# 6__FAN_ADC_LED.net
KiCad netlist of a schematic drawn in Altium Designer
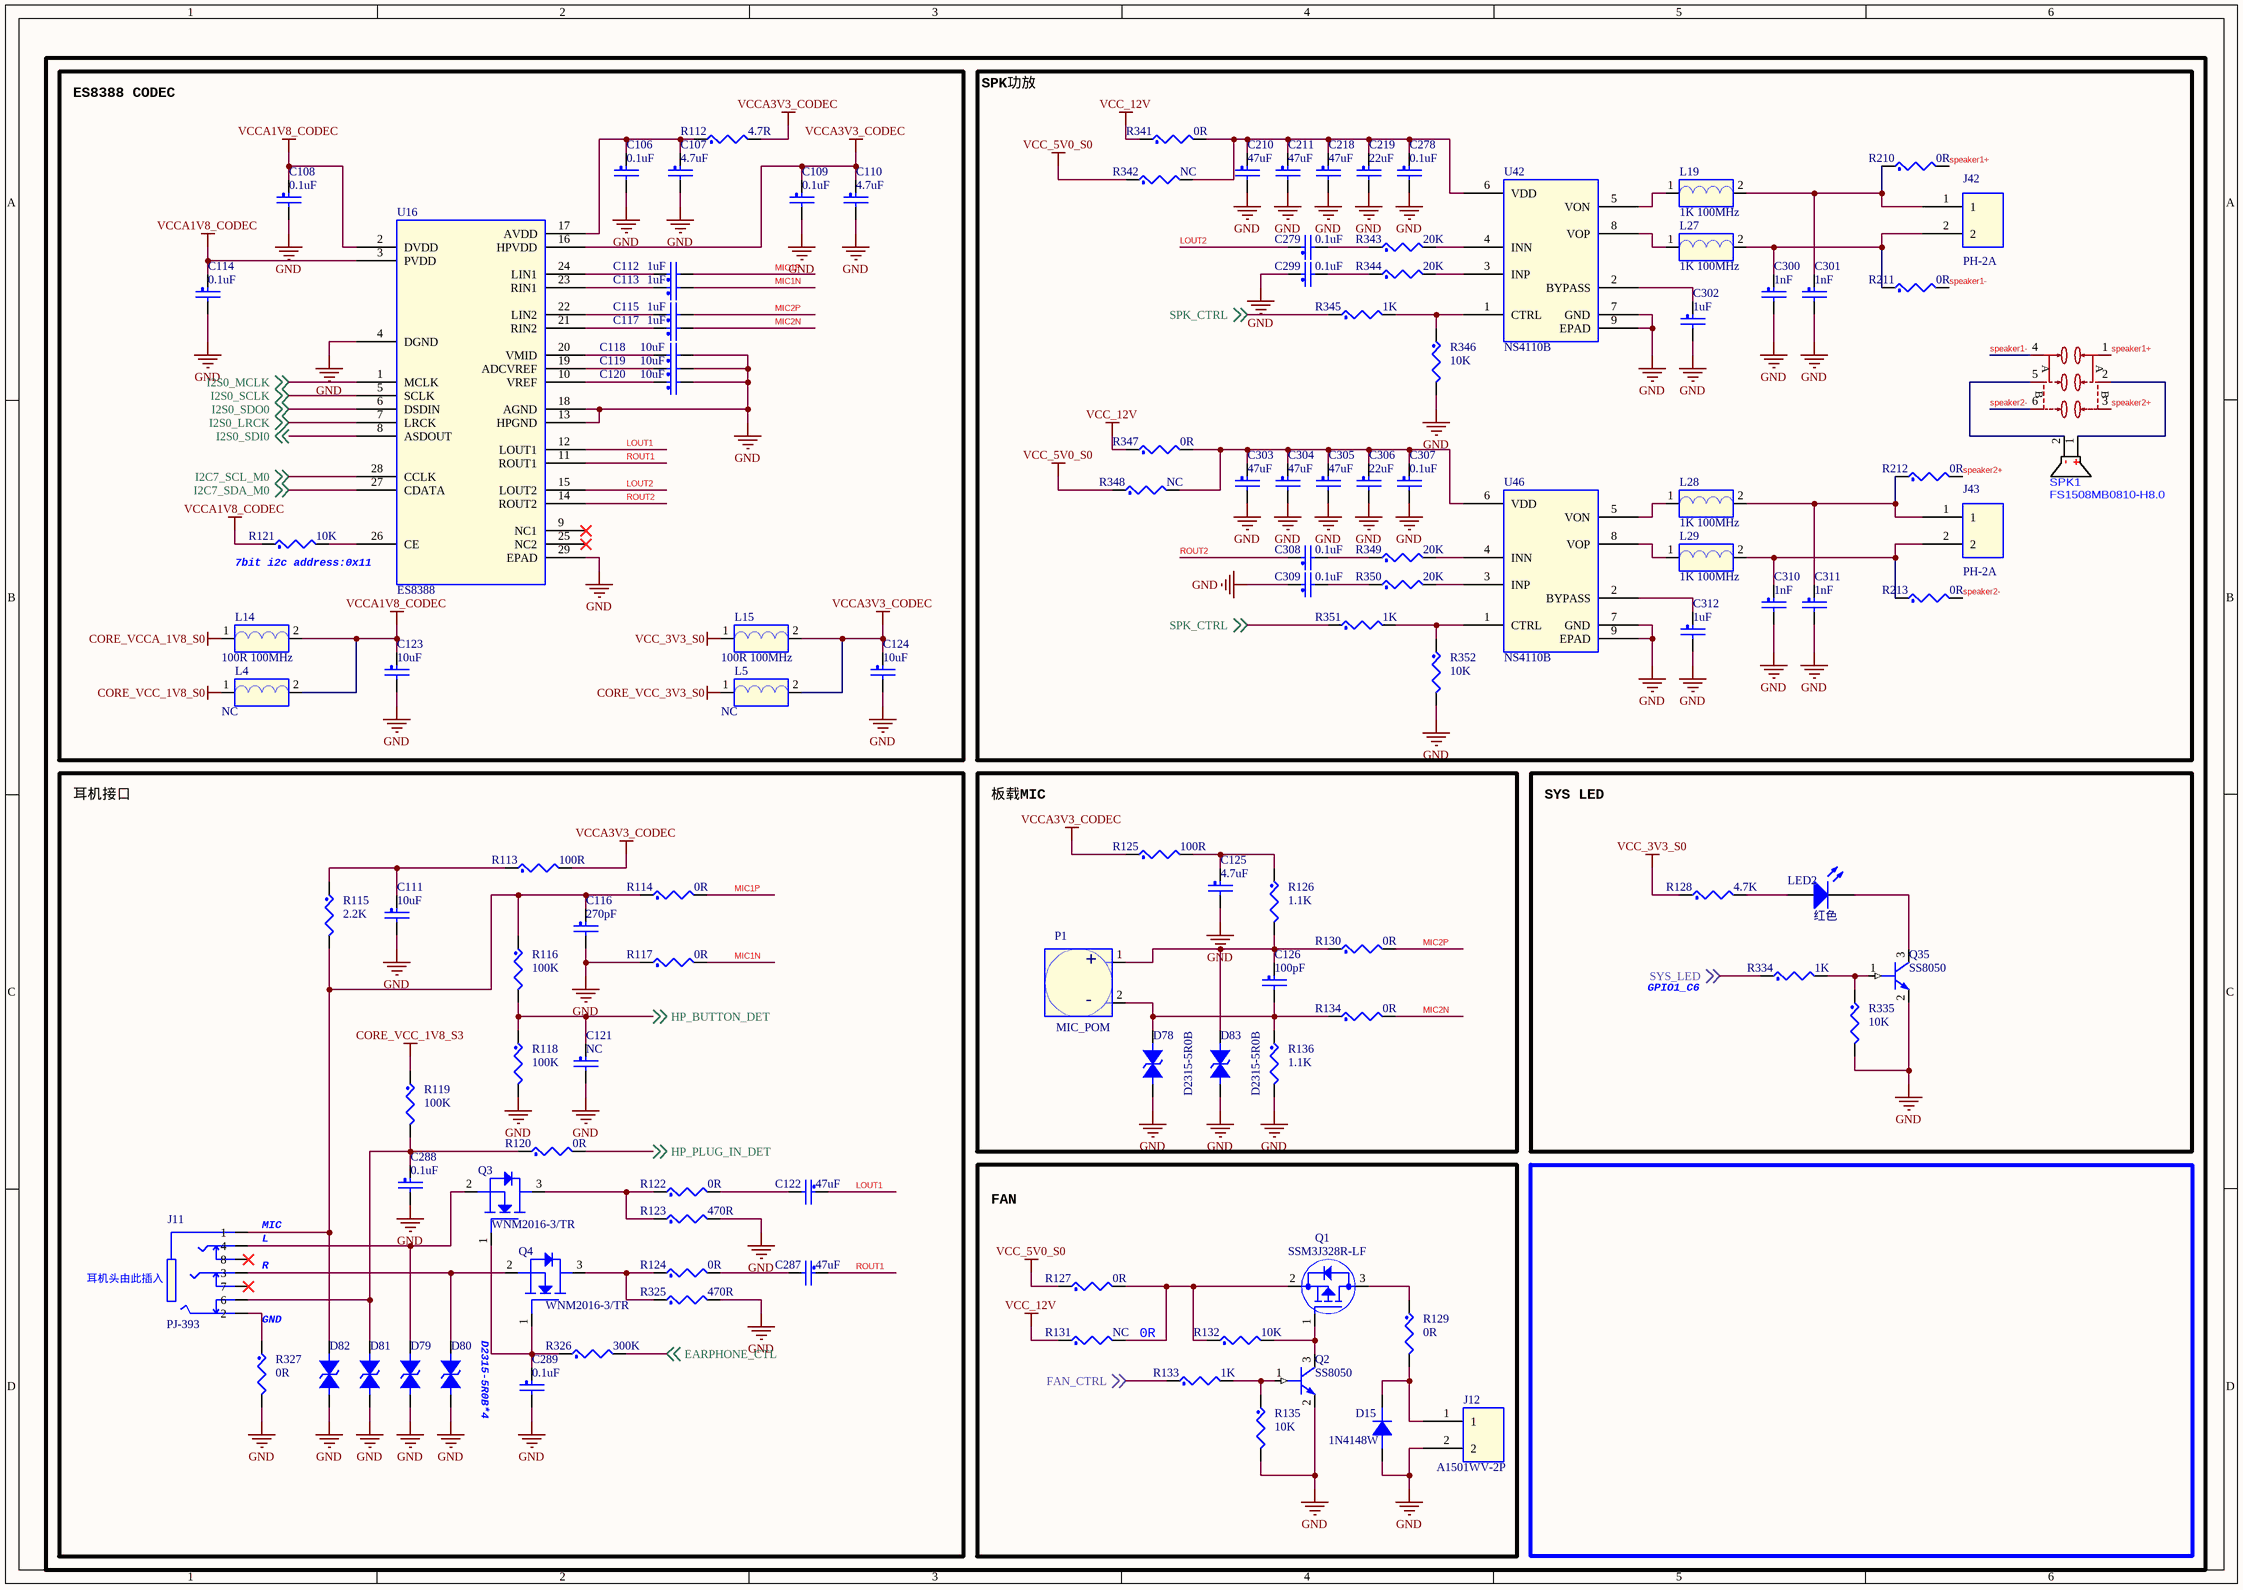
[diagram p0: 6.音频_FAN_ADC_LED.SchDoc]

(export (version "E")
  (design (tool "Eeschema 10.0.6"))
  (components
    (comp (ref "C106")
      (value "0.1uF")
      (footprint "0.PCB1:C0402")
      (libsource (lib "RK3588底板") (part "CAP_NP"))
    )
    (comp (ref "C107")
      (value "4.7uF")
      (footprint "0.PCB1:C0402")
      (libsource (lib "RK3588底板") (part "CAP_NP"))
    )
    (comp (ref "C108")
      (value "0.1uF")
      (footprint "0.PCB1:C0402")
      (libsource (lib "RK3588底板") (part "CAP_NP"))
    )
    (comp (ref "C109")
      (value "0.1uF")
      (footprint "0.PCB1:C0402")
      (libsource (lib "RK3588底板") (part "CAP_NP"))
    )
    (comp (ref "C110")
      (value "4.7uF")
      (footprint "0.PCB1:C0402")
      (libsource (lib "RK3588底板") (part "CAP_NP"))
    )
    (comp (ref "C111") (value "10uF") (footprint "0.PCB1:C0402") (libsource (lib "RK3588底板") (part "CAP_NP")))
    (comp (ref "C112") (value "1uF") (footprint "0.PCB1:C0402") (libsource (lib "RK3588底板") (part "CAP_NP")))
    (comp (ref "C113") (value "1uF") (footprint "0.PCB1:C0402") (libsource (lib "RK3588底板") (part "CAP_NP")))
    (comp (ref "C114")
      (value "0.1uF")
      (footprint "0.PCB1:C0402")
      (libsource (lib "RK3588底板") (part "CAP_NP"))
    )
    (comp (ref "C115") (value "1uF") (footprint "0.PCB1:C0402") (libsource (lib "RK3588底板") (part "CAP_NP")))
    (comp (ref "C116")
      (value "270pF")
      (footprint "0.PCB1:C0402")
      (libsource (lib "RK3588底板") (part "CAP_NP"))
    )
    (comp (ref "C117") (value "1uF") (footprint "0.PCB1:C0402") (libsource (lib "RK3588底板") (part "CAP_NP")))
    (comp (ref "C118") (value "10uF") (footprint "0.PCB1:C0402") (libsource (lib "RK3588底板") (part "CAP_NP")))
    (comp (ref "C119") (value "10uF") (footprint "0.PCB1:C0402") (libsource (lib "RK3588底板") (part "CAP_NP")))
    (comp (ref "C120") (value "10uF") (footprint "0.PCB1:C0402") (libsource (lib "RK3588底板") (part "CAP_NP")))
    (comp (ref "C121") (value "NC") (footprint "0.PCB1:C0402") (libsource (lib "RK3588底板") (part "CAP_NP")))
    (comp (ref "C122") (value "47uF") (footprint "0.PCB1:C0603") (libsource (lib "RK3588底板") (part "CAP_NP")))
    (comp (ref "C123") (value "10uF") (footprint "0.PCB1:C0402") (libsource (lib "RK3588底板") (part "CAP_NP")))
    (comp (ref "C124") (value "10uF") (footprint "0.PCB1:C0402") (libsource (lib "RK3588底板") (part "CAP_NP")))
    (comp (ref "C125")
      (value "4.7uF")
      (footprint "0.PCB1:C0402")
      (libsource (lib "RK3588底板") (part "CAP_NP"))
    )
    (comp (ref "C126")
      (value "100pF")
      (footprint "0.PCB1:C0402")
      (libsource (lib "RK3588底板") (part "CAP_NP"))
    )
    (comp (ref "C210") (value "47uF") (footprint "0.PCB1:C1206") (libsource (lib "RK3588底板") (part "CAP_NP")))
    (comp (ref "C211") (value "47uF") (footprint "0.PCB1:C1206") (libsource (lib "RK3588底板") (part "CAP_NP")))
    (comp (ref "C218") (value "47uF") (footprint "0.PCB1:C1206") (libsource (lib "RK3588底板") (part "CAP_NP")))
    (comp (ref "C219") (value "22uF") (footprint "0.PCB1:C0805") (libsource (lib "RK3588底板") (part "CAP_NP")))
    (comp (ref "C278")
      (value "0.1uF")
      (footprint "0.PCB1:C0402")
      (libsource (lib "RK3588底板") (part "CAP_NP"))
    )
    (comp (ref "C279")
      (value "0.1uF")
      (footprint "0.PCB1:C0402")
      (libsource (lib "RK3588底板") (part "CAP_NP"))
    )
    (comp (ref "C287") (value "47uF") (footprint "0.PCB1:C0603") (libsource (lib "RK3588底板") (part "CAP_NP")))
    (comp (ref "C288")
      (value "0.1uF")
      (footprint "0.PCB1:C0402")
      (libsource (lib "RK3588底板") (part "CAP_NP"))
    )
    (comp (ref "C289")
      (value "0.1uF")
      (footprint "0.PCB1:C0402")
      (libsource (lib "RK3588底板") (part "CAP_NP"))
    )
    (comp (ref "C299")
      (value "0.1uF")
      (footprint "0.PCB1:C0402")
      (libsource (lib "RK3588底板") (part "CAP_NP"))
    )
    (comp (ref "C300") (value "1nF") (footprint "0.PCB1:C0402") (libsource (lib "RK3588底板") (part "CAP_NP")))
    (comp (ref "C301") (value "1nF") (footprint "0.PCB1:C0402") (libsource (lib "RK3588底板") (part "CAP_NP")))
    (comp (ref "C302") (value "1uF") (footprint "0.PCB1:C0402") (libsource (lib "RK3588底板") (part "CAP_NP")))
    (comp (ref "C303") (value "47uF") (footprint "0.PCB1:C1206") (libsource (lib "RK3588底板") (part "CAP_NP")))
    (comp (ref "C304") (value "47uF") (footprint "0.PCB1:C1206") (libsource (lib "RK3588底板") (part "CAP_NP")))
    (comp (ref "C305") (value "47uF") (footprint "0.PCB1:C1206") (libsource (lib "RK3588底板") (part "CAP_NP")))
    (comp (ref "C306") (value "22uF") (footprint "0.PCB1:C0805") (libsource (lib "RK3588底板") (part "CAP_NP")))
    (comp (ref "C307")
      (value "0.1uF")
      (footprint "0.PCB1:C0402")
      (libsource (lib "RK3588底板") (part "CAP_NP"))
    )
    (comp (ref "C308")
      (value "0.1uF")
      (footprint "0.PCB1:C0402")
      (libsource (lib "RK3588底板") (part "CAP_NP"))
    )
    (comp (ref "C309")
      (value "0.1uF")
      (footprint "0.PCB1:C0402")
      (libsource (lib "RK3588底板") (part "CAP_NP"))
    )
    (comp (ref "C310") (value "1nF") (footprint "0.PCB1:C0402") (libsource (lib "RK3588底板") (part "CAP_NP")))
    (comp (ref "C311") (value "1nF") (footprint "0.PCB1:C0402") (libsource (lib "RK3588底板") (part "CAP_NP")))
    (comp (ref "C312") (value "1uF") (footprint "0.PCB1:C0402") (libsource (lib "RK3588底板") (part "CAP_NP")))
    (comp (ref "D15")
      (value "1N4148W")
      (footprint "0.PCB1:SOD-123")
      (libsource (lib "RK3588底板") (part "DIODE"))
    )
    (comp (ref "D78")
      (value "D2315-5R0B")
      (footprint "0.PCB1:esd0402")
      (libsource (lib "RK3588底板") (part "DIODE BI-DIR TRIG"))
    )
    (comp (ref "D79")
      (value "D2315-5R0B")
      (footprint "0.PCB1:esd0402")
      (libsource (lib "RK3588底板") (part "DIODE BI-DIR TRIG"))
    )
    (comp (ref "D80")
      (value "D2315-5R0B")
      (footprint "0.PCB1:esd0402")
      (libsource (lib "RK3588底板") (part "DIODE BI-DIR TRIG"))
    )
    (comp (ref "D81")
      (value "D2315-5R0B")
      (footprint "0.PCB1:esd0402")
      (libsource (lib "RK3588底板") (part "DIODE BI-DIR TRIG"))
    )
    (comp (ref "D82")
      (value "D2315-5R0B")
      (footprint "0.PCB1:esd0402")
      (libsource (lib "RK3588底板") (part "DIODE BI-DIR TRIG"))
    )
    (comp (ref "D83")
      (value "D2315-5R0B")
      (footprint "0.PCB1:esd0402")
      (libsource (lib "RK3588底板") (part "DIODE BI-DIR TRIG"))
    )
    (comp (ref "J11")
      (value "PJ-393")
      (footprint "0.PCB1:audio_smd_7p_6r0x8r8")
      (libsource (lib "RK3588底板") (part "PJ-393"))
    )
    (comp (ref "J12")
      (value "A1501WV-2P")
      (footprint "0.PCB1:zh1p5mm_th_2p")
      (libsource (lib "RK3588底板") (part "1X2PIN"))
    )
    (comp (ref "J42")
      (value "PH-2A")
      (footprint "0.PCB1:PH-1x2-2P0_l")
      (libsource (lib "RK3588底板") (part "1X2PIN"))
    )
    (comp (ref "J43")
      (value "PH-2A")
      (footprint "0.PCB1:PH-1x2-2P0_l")
      (libsource (lib "RK3588底板") (part "1X2PIN"))
    )
    (comp (ref "L4") (value "NC") (footprint "0.PCB1:L0603") (libsource (lib "RK3588底板") (part "BEAD")))
    (comp (ref "L5") (value "NC") (footprint "0.PCB1:L0603") (libsource (lib "RK3588底板") (part "BEAD")))
    (comp (ref "L14")
      (value "100R 100MHz")
      (footprint "0.PCB1:L0603")
      (libsource (lib "RK3588底板") (part "BEAD"))
    )
    (comp (ref "L15")
      (value "100R 100MHz")
      (footprint "0.PCB1:L0603")
      (libsource (lib "RK3588底板") (part "BEAD"))
    )
    (comp (ref "L19")
      (value "1K 100MHz")
      (footprint "0.PCB1:L0603")
      (libsource (lib "RK3588底板") (part "BEAD"))
    )
    (comp (ref "L27")
      (value "1K 100MHz")
      (footprint "0.PCB1:L0603")
      (libsource (lib "RK3588底板") (part "BEAD"))
    )
    (comp (ref "L28")
      (value "1K 100MHz")
      (footprint "0.PCB1:L0603")
      (libsource (lib "RK3588底板") (part "BEAD"))
    )
    (comp (ref "L29")
      (value "1K 100MHz")
      (footprint "0.PCB1:L0603")
      (libsource (lib "RK3588底板") (part "BEAD"))
    )
    (comp (ref "LED2")
      (value "红色")
      (footprint "0.PCB1:LED0603_R")
      (description "贴片LED")
      (libsource (lib "RK3588底板") (part "LED"))
    )
    (comp (ref "P1")
      (value "MIC_POM")
      (footprint "0.PCB1:MIC2-4R00-TM")
      (libsource (lib "RK3588底板") (part "MIC_POM"))
    )
    (comp (ref "Q1")
      (value "SSM3J328R-LF")
      (footprint "0.PCB1:SOT23")
      (libsource (lib "RK3588底板") (part "MOSFET_P"))
    )
    (comp (ref "Q2") (value "SS8050") (footprint "0.PCB1:SOT23") (libsource (lib "RK3588底板") (part "NPN")))
    (comp (ref "Q3")
      (value "WNM2016-3/TR")
      (footprint "0.PCB1:SOT23")
      (libsource (lib "RK3588底板") (part "MOSFET N"))
    )
    (comp (ref "Q4")
      (value "WNM2016-3/TR")
      (footprint "0.PCB1:SOT23")
      (libsource (lib "RK3588底板") (part "MOSFET N"))
    )
    (comp (ref "Q35") (value "SS8050") (footprint "0.PCB1:SOT23") (libsource (lib "RK3588底板") (part "NPN")))
    (comp (ref "R112") (value "4.7R") (footprint "0.PCB1:R0402") (libsource (lib "RK3588底板") (part "RES")))
    (comp (ref "R113") (value "100R") (footprint "0.PCB1:R0402") (libsource (lib "RK3588底板") (part "RES")))
    (comp (ref "R114") (value "0R") (footprint "0.PCB1:R0402") (libsource (lib "RK3588底板") (part "RES")))
    (comp (ref "R115") (value "2.2K") (footprint "0.PCB1:R0402") (libsource (lib "RK3588底板") (part "RES")))
    (comp (ref "R116") (value "100K") (footprint "0.PCB1:R0402") (libsource (lib "RK3588底板") (part "RES")))
    (comp (ref "R117") (value "0R") (footprint "0.PCB1:R0402") (libsource (lib "RK3588底板") (part "RES")))
    (comp (ref "R118") (value "100K") (footprint "0.PCB1:R0402") (libsource (lib "RK3588底板") (part "RES")))
    (comp (ref "R119") (value "100K") (footprint "0.PCB1:R0402") (libsource (lib "RK3588底板") (part "RES")))
    (comp (ref "R120") (value "0R") (footprint "0.PCB1:R0402") (libsource (lib "RK3588底板") (part "RES")))
    (comp (ref "R121") (value "10K") (footprint "0.PCB1:R0402") (libsource (lib "RK3588底板") (part "RES")))
    (comp (ref "R122") (value "0R") (footprint "0.PCB1:R0402") (libsource (lib "RK3588底板") (part "RES")))
    (comp (ref "R123") (value "470R") (footprint "0.PCB1:R0402") (libsource (lib "RK3588底板") (part "RES")))
    (comp (ref "R124") (value "0R") (footprint "0.PCB1:R0402") (libsource (lib "RK3588底板") (part "RES")))
    (comp (ref "R125") (value "100R") (footprint "0.PCB1:R0402") (libsource (lib "RK3588底板") (part "RES")))
    (comp (ref "R126") (value "1.1K") (footprint "0.PCB1:R0402") (libsource (lib "RK3588底板") (part "RES")))
    (comp (ref "R127") (value "0R") (footprint "0.PCB1:R0805") (libsource (lib "RK3588底板") (part "RES")))
    (comp (ref "R128") (value "4.7K") (footprint "0.PCB1:R0402") (libsource (lib "RK3588底板") (part "RES")))
    (comp (ref "R129") (value "0R") (footprint "0.PCB1:R0805") (libsource (lib "RK3588底板") (part "RES")))
    (comp (ref "R130") (value "0R") (footprint "0.PCB1:R0402") (libsource (lib "RK3588底板") (part "RES")))
    (comp (ref "R131") (value "NC") (footprint "0.PCB1:R0805") (libsource (lib "RK3588底板") (part "RES")))
    (comp (ref "R132") (value "10K") (footprint "0.PCB1:R0402") (libsource (lib "RK3588底板") (part "RES")))
    (comp (ref "R133") (value "1K") (footprint "0.PCB1:R0402") (libsource (lib "RK3588底板") (part "RES")))
    (comp (ref "R134") (value "0R") (footprint "0.PCB1:R0402") (libsource (lib "RK3588底板") (part "RES")))
    (comp (ref "R135") (value "10K") (footprint "0.PCB1:R0402") (libsource (lib "RK3588底板") (part "RES")))
    (comp (ref "R136") (value "1.1K") (footprint "0.PCB1:R0402") (libsource (lib "RK3588底板") (part "RES")))
    (comp (ref "R210") (value "0R") (footprint "0.PCB1:R0805") (libsource (lib "RK3588底板") (part "RES")))
    (comp (ref "R211") (value "0R") (footprint "0.PCB1:R0805") (libsource (lib "RK3588底板") (part "RES")))
    (comp (ref "R212") (value "0R") (footprint "0.PCB1:R0805") (libsource (lib "RK3588底板") (part "RES")))
    (comp (ref "R213") (value "0R") (footprint "0.PCB1:R0805") (libsource (lib "RK3588底板") (part "RES")))
    (comp (ref "R325") (value "470R") (footprint "0.PCB1:R0402") (libsource (lib "RK3588底板") (part "RES")))
    (comp (ref "R326") (value "300K") (footprint "0.PCB1:R0402") (libsource (lib "RK3588底板") (part "RES")))
    (comp (ref "R327") (value "0R") (footprint "0.PCB1:R0402") (libsource (lib "RK3588底板") (part "RES")))
    (comp (ref "R334") (value "1K") (footprint "0.PCB1:R0402") (libsource (lib "RK3588底板") (part "RES")))
    (comp (ref "R335") (value "10K") (footprint "0.PCB1:R0402") (libsource (lib "RK3588底板") (part "RES")))
    (comp (ref "R341") (value "0R") (footprint "0.PCB1:R0603") (libsource (lib "RK3588底板") (part "RES")))
    (comp (ref "R342") (value "NC") (footprint "0.PCB1:R0603") (libsource (lib "RK3588底板") (part "RES")))
    (comp (ref "R343") (value "20K") (footprint "0.PCB1:R0402") (libsource (lib "RK3588底板") (part "RES")))
    (comp (ref "R344") (value "20K") (footprint "0.PCB1:R0402") (libsource (lib "RK3588底板") (part "RES")))
    (comp (ref "R345") (value "1K") (footprint "0.PCB1:R0402") (libsource (lib "RK3588底板") (part "RES")))
    (comp (ref "R346") (value "10K") (footprint "0.PCB1:R0402") (libsource (lib "RK3588底板") (part "RES")))
    (comp (ref "R347") (value "0R") (footprint "0.PCB1:R0603") (libsource (lib "RK3588底板") (part "RES")))
    (comp (ref "R348") (value "NC") (footprint "0.PCB1:R0603") (libsource (lib "RK3588底板") (part "RES")))
    (comp (ref "R349") (value "20K") (footprint "0.PCB1:R0402") (libsource (lib "RK3588底板") (part "RES")))
    (comp (ref "R350") (value "20K") (footprint "0.PCB1:R0402") (libsource (lib "RK3588底板") (part "RES")))
    (comp (ref "R351") (value "1K") (footprint "0.PCB1:R0402") (libsource (lib "RK3588底板") (part "RES")))
    (comp (ref "R352") (value "10K") (footprint "0.PCB1:R0402") (libsource (lib "RK3588底板") (part "RES")))
    (comp (ref "SPK1")
      (value "FS1508MB0810-H8.0")
      (footprint "0.PCB1:BEEP-TH_BD15.0-P10.20-D1.2")
      (libsource (lib "RK3588底板") (part "FS1508MB0810-H8.0"))
    )
    (comp (ref "SW5")
      (value "MST22D18G2")
      (footprint "0.PCB1:SW-SMD_MST22D18G2")
      (libsource (lib "RK3588底板") (part "MST22D18G2"))
    )
    (comp (ref "U16")
      (value "ES8388")
      (footprint "0.PCB1:qfn28_0r45-4x4EP2R6X2R6")
      (libsource (lib "RK3588底板") (part "ES8388"))
    )
    (comp (ref "U42")
      (value "NS4110B")
      (footprint "0.PCB1:SOP-8-EP-2R5X3R4")
      (libsource (lib "RK3588底板") (part "NS4110B"))
    )
    (comp (ref "U46")
      (value "NS4110B")
      (footprint "0.PCB1:SOP-8-EP-2R5X3R4")
      (libsource (lib "RK3588底板") (part "NS4110B"))
    )
  )
  (nets
    (net (code "1") (name "/LOUT1") (class "Default")
      (node (ref "C122") (pin "1") (pinfunction "1_1") (pintype "passive"))
      (node (ref "U16") (pin "12") (pinfunction "LOUT1_12") (pintype "passive"))
    )
    (net (code "2") (name "/LOUT2") (class "Default")
      (node (ref "C279") (pin "1") (pinfunction "1_1") (pintype "passive"))
      (node (ref "U16") (pin "15") (pinfunction "LOUT2_15") (pintype "passive"))
    )
    (net (code "3") (name "/MIC1N") (class "Default")
      (node (ref "C113") (pin "2") (pinfunction "2_2") (pintype "passive"))
      (node (ref "R117") (pin "2") (pinfunction "2_2") (pintype "passive"))
    )
    (net (code "4") (name "/MIC1P") (class "Default")
      (node (ref "C112") (pin "2") (pinfunction "2_2") (pintype "passive"))
      (node (ref "R114") (pin "2") (pinfunction "2_2") (pintype "passive"))
    )
    (net (code "5") (name "/MIC2N") (class "Default")
      (node (ref "C117") (pin "2") (pinfunction "2_2") (pintype "passive"))
      (node (ref "R134") (pin "2") (pinfunction "2_2") (pintype "passive"))
    )
    (net (code "6") (name "/MIC2P") (class "Default")
      (node (ref "C115") (pin "2") (pinfunction "2_2") (pintype "passive"))
      (node (ref "R130") (pin "2") (pinfunction "2_2") (pintype "passive"))
    )
    (net (code "7") (name "/ROUT1") (class "Default")
      (node (ref "C287") (pin "1") (pinfunction "1_1") (pintype "passive"))
      (node (ref "U16") (pin "11") (pinfunction "ROUT1_11") (pintype "passive"))
    )
    (net (code "8") (name "/ROUT2") (class "Default")
      (node (ref "C308") (pin "1") (pinfunction "1_1") (pintype "passive"))
      (node (ref "U16") (pin "14") (pinfunction "ROUT2_14") (pintype "passive"))
    )
    (net (code "9") (name "/speaker1+") (class "Default")
      (node (ref "R210") (pin "2") (pinfunction "2_2") (pintype "passive"))
      (node (ref "SW5") (pin "1") (pinfunction "1_1") (pintype "passive"))
    )
    (net (code "10") (name "/speaker1-") (class "Default")
      (node (ref "R211") (pin "2") (pinfunction "2_2") (pintype "passive"))
      (node (ref "SW5") (pin "4") (pinfunction "4_4") (pintype "passive"))
    )
    (net (code "11") (name "/speaker2+") (class "Default")
      (node (ref "R212") (pin "2") (pinfunction "2_2") (pintype "passive"))
      (node (ref "SW5") (pin "3") (pinfunction "3_3") (pintype "passive"))
    )
    (net (code "12") (name "/speaker2-") (class "Default")
      (node (ref "R213") (pin "2") (pinfunction "2_2") (pintype "passive"))
      (node (ref "SW5") (pin "6") (pinfunction "6_6") (pintype "passive"))
    )
    (net (code "13") (name "CORE_VCCA_1V8_S0") (class "Default")
      (node (ref "L14") (pin "1") (pinfunction "1_1") (pintype "passive"))
    )
    (net (code "14") (name "CORE_VCC_1V8_S0") (class "Default")
      (node (ref "L4") (pin "1") (pinfunction "1_1") (pintype "passive"))
    )
    (net (code "15") (name "CORE_VCC_1V8_S3") (class "Default")
      (node (ref "R119") (pin "1") (pinfunction "1_1") (pintype "passive"))
    )
    (net (code "16") (name "CORE_VCC_3V3_S0") (class "Default")
      (node (ref "L5") (pin "1") (pinfunction "1_1") (pintype "passive"))
    )
    (net (code "17") (name "EARPHONE_CTL") (class "Default")
      (node (ref "R326") (pin "2") (pinfunction "2_2") (pintype "passive"))
    )
    (net (code "18") (name "FAN_CTRL") (class "Default")
      (node (ref "R133") (pin "1") (pinfunction "1_1") (pintype "passive"))
    )
    (net (code "19") (name "GND") (class "Default")
      (node (ref "C106") (pin "2") (pinfunction "2_2") (pintype "passive"))
      (node (ref "C107") (pin "2") (pinfunction "2_2") (pintype "passive"))
      (node (ref "C108") (pin "2") (pinfunction "2_2") (pintype "passive"))
      (node (ref "C109") (pin "2") (pinfunction "2_2") (pintype "passive"))
      (node (ref "C110") (pin "2") (pinfunction "2_2") (pintype "passive"))
      (node (ref "C111") (pin "2") (pinfunction "2_2") (pintype "passive"))
      (node (ref "C114") (pin "2") (pinfunction "2_2") (pintype "passive"))
      (node (ref "C116") (pin "2") (pinfunction "2_2") (pintype "passive"))
      (node (ref "C118") (pin "2") (pinfunction "2_2") (pintype "passive"))
      (node (ref "C119") (pin "2") (pinfunction "2_2") (pintype "passive"))
      (node (ref "C120") (pin "2") (pinfunction "2_2") (pintype "passive"))
      (node (ref "C121") (pin "2") (pinfunction "2_2") (pintype "passive"))
      (node (ref "C123") (pin "2") (pinfunction "2_2") (pintype "passive"))
      (node (ref "C124") (pin "2") (pinfunction "2_2") (pintype "passive"))
      (node (ref "C125") (pin "2") (pinfunction "2_2") (pintype "passive"))
      (node (ref "C210") (pin "2") (pinfunction "2_2") (pintype "passive"))
      (node (ref "C211") (pin "2") (pinfunction "2_2") (pintype "passive"))
      (node (ref "C218") (pin "2") (pinfunction "2_2") (pintype "passive"))
      (node (ref "C219") (pin "2") (pinfunction "2_2") (pintype "passive"))
      (node (ref "C278") (pin "2") (pinfunction "2_2") (pintype "passive"))
      (node (ref "C288") (pin "2") (pinfunction "2_2") (pintype "passive"))
      (node (ref "C289") (pin "2") (pinfunction "2_2") (pintype "passive"))
      (node (ref "C299") (pin "1") (pinfunction "1_1") (pintype "passive"))
      (node (ref "C300") (pin "2") (pinfunction "2_2") (pintype "passive"))
      (node (ref "C301") (pin "2") (pinfunction "2_2") (pintype "passive"))
      (node (ref "C302") (pin "2") (pinfunction "2_2") (pintype "passive"))
      (node (ref "C303") (pin "2") (pinfunction "2_2") (pintype "passive"))
      (node (ref "C304") (pin "2") (pinfunction "2_2") (pintype "passive"))
      (node (ref "C305") (pin "2") (pinfunction "2_2") (pintype "passive"))
      (node (ref "C306") (pin "2") (pinfunction "2_2") (pintype "passive"))
      (node (ref "C307") (pin "2") (pinfunction "2_2") (pintype "passive"))
      (node (ref "C309") (pin "1") (pinfunction "1_1") (pintype "passive"))
      (node (ref "C310") (pin "2") (pinfunction "2_2") (pintype "passive"))
      (node (ref "C311") (pin "2") (pinfunction "2_2") (pintype "passive"))
      (node (ref "C312") (pin "2") (pinfunction "2_2") (pintype "passive"))
      (node (ref "D15") (pin "2") (pinfunction "A_2") (pintype "passive"))
      (node (ref "D78") (pin "1") (pinfunction "1_1") (pintype "passive"))
      (node (ref "D79") (pin "1") (pinfunction "1_1") (pintype "passive"))
      (node (ref "D80") (pin "1") (pinfunction "1_1") (pintype "passive"))
      (node (ref "D81") (pin "1") (pinfunction "1_1") (pintype "passive"))
      (node (ref "D82") (pin "1") (pinfunction "1_1") (pintype "passive"))
      (node (ref "D83") (pin "1") (pinfunction "1_1") (pintype "passive"))
      (node (ref "J12") (pin "2") (pinfunction "2_2") (pintype "passive"))
      (node (ref "Q2") (pin "2") (pinfunction "EMITTER_2") (pintype "passive"))
      (node (ref "Q35") (pin "2") (pinfunction "EMITTER_2") (pintype "passive"))
      (node (ref "R117") (pin "1") (pinfunction "1_1") (pintype "passive"))
      (node (ref "R118") (pin "2") (pinfunction "2_2") (pintype "passive"))
      (node (ref "R123") (pin "2") (pinfunction "2_2") (pintype "passive"))
      (node (ref "R135") (pin "2") (pinfunction "2_2") (pintype "passive"))
      (node (ref "R136") (pin "2") (pinfunction "2_2") (pintype "passive"))
      (node (ref "R325") (pin "2") (pinfunction "2_2") (pintype "passive"))
      (node (ref "R327") (pin "2") (pinfunction "2_2") (pintype "passive"))
      (node (ref "R335") (pin "2") (pinfunction "2_2") (pintype "passive"))
      (node (ref "R346") (pin "2") (pinfunction "2_2") (pintype "passive"))
      (node (ref "R352") (pin "2") (pinfunction "2_2") (pintype "passive"))
      (node (ref "U16") (pin "13") (pinfunction "HPGND_13") (pintype "passive"))
      (node (ref "U16") (pin "18") (pinfunction "AGND_18") (pintype "passive"))
      (node (ref "U16") (pin "29") (pinfunction "EPAD_29") (pintype "passive"))
      (node (ref "U16") (pin "4") (pinfunction "DGND_4") (pintype "passive"))
      (node (ref "U42") (pin "7") (pinfunction "GND_7") (pintype "passive"))
      (node (ref "U42") (pin "9") (pinfunction "EPAD_9") (pintype "passive"))
      (node (ref "U46") (pin "7") (pinfunction "GND_7") (pintype "passive"))
      (node (ref "U46") (pin "9") (pinfunction "EPAD_9") (pintype "passive"))
    )
    (net (code "20") (name "HP_BUTTON_DET") (class "Default")
      (node (ref "C121") (pin "1") (pinfunction "1_1") (pintype "passive"))
      (node (ref "R116") (pin "2") (pinfunction "2_2") (pintype "passive"))
      (node (ref "R118") (pin "1") (pinfunction "1_1") (pintype "passive"))
    )
    (net (code "21") (name "HP_PLUG_IN_DET") (class "Default")
      (node (ref "R120") (pin "2") (pinfunction "2_2") (pintype "passive"))
    )
    (net (code "22") (name "I2C7_SCL_M0") (class "Default")
      (node (ref "U16") (pin "28") (pinfunction "CCLK_28") (pintype "passive"))
    )
    (net (code "23") (name "I2C7_SDA_M0") (class "Default")
      (node (ref "U16") (pin "27") (pinfunction "CDATA_27") (pintype "passive"))
    )
    (net (code "24") (name "I2S0_LRCK") (class "Default")
      (node (ref "U16") (pin "7") (pinfunction "LRCK_7") (pintype "passive"))
    )
    (net (code "25") (name "I2S0_MCLK") (class "Default")
      (node (ref "U16") (pin "1") (pinfunction "MCLK_1") (pintype "passive"))
    )
    (net (code "26") (name "I2S0_SCLK") (class "Default")
      (node (ref "U16") (pin "5") (pinfunction "SCLK_5") (pintype "passive"))
    )
    (net (code "27") (name "I2S0_SDI0") (class "Default")
      (node (ref "U16") (pin "8") (pinfunction "ASDOUT_8") (pintype "passive"))
    )
    (net (code "28") (name "I2S0_SDO0") (class "Default")
      (node (ref "U16") (pin "6") (pinfunction "DSDIN_6") (pintype "passive"))
    )
    (net (code "29") (name "Net-(C111-Pad1)") (class "Default")
      (node (ref "C111") (pin "1") (pinfunction "1_1") (pintype "passive"))
      (node (ref "R113") (pin "1") (pinfunction "1_1") (pintype "passive"))
      (node (ref "R115") (pin "1") (pinfunction "1_1") (pintype "passive"))
    )
    (net (code "30") (name "Net-(C116-Pad1)") (class "Default")
      (node (ref "C116") (pin "1") (pinfunction "1_1") (pintype "passive"))
      (node (ref "D82") (pin "2") (pinfunction "2_2") (pintype "passive"))
      (node (ref "J11") (pin "1") (pinfunction "1_1") (pintype "passive"))
      (node (ref "R114") (pin "1") (pinfunction "1_1") (pintype "passive"))
      (node (ref "R115") (pin "2") (pinfunction "2_2") (pintype "passive"))
      (node (ref "R116") (pin "1") (pinfunction "1_1") (pintype "passive"))
    )
    (net (code "31") (name "Net-(C122-Pad2)") (class "Default")
      (node (ref "C122") (pin "2") (pinfunction "2_2") (pintype "passive"))
      (node (ref "R122") (pin "2") (pinfunction "2_2") (pintype "passive"))
    )
    (net (code "32") (name "Net-(C125-Pad1)") (class "Default")
      (node (ref "C125") (pin "1") (pinfunction "1_1") (pintype "passive"))
      (node (ref "R125") (pin "2") (pinfunction "2_2") (pintype "passive"))
      (node (ref "R126") (pin "1") (pinfunction "1_1") (pintype "passive"))
    )
    (net (code "33") (name "Net-(C279-Pad2)") (class "Default")
      (node (ref "C279") (pin "2") (pinfunction "2_2") (pintype "passive"))
      (node (ref "R343") (pin "1") (pinfunction "1_1") (pintype "passive"))
    )
    (net (code "34") (name "Net-(C287-Pad2)") (class "Default")
      (node (ref "C287") (pin "2") (pinfunction "2_2") (pintype "passive"))
      (node (ref "R124") (pin "2") (pinfunction "2_2") (pintype "passive"))
    )
    (net (code "35") (name "Net-(C288-Pad1)") (class "Default")
      (node (ref "C288") (pin "1") (pinfunction "1_1") (pintype "passive"))
      (node (ref "D81") (pin "2") (pinfunction "2_2") (pintype "passive"))
      (node (ref "J11") (pin "6") (pinfunction "6_6") (pintype "passive"))
      (node (ref "R119") (pin "2") (pinfunction "2_2") (pintype "passive"))
      (node (ref "R120") (pin "1") (pinfunction "1_1") (pintype "passive"))
    )
    (net (code "36") (name "Net-(C299-Pad2)") (class "Default")
      (node (ref "C299") (pin "2") (pinfunction "2_2") (pintype "passive"))
      (node (ref "R344") (pin "1") (pinfunction "1_1") (pintype "passive"))
    )
    (net (code "37") (name "Net-(C300-Pad1)") (class "Default")
      (node (ref "C300") (pin "1") (pinfunction "1_1") (pintype "passive"))
      (node (ref "J42") (pin "2") (pinfunction "2_2") (pintype "passive"))
      (node (ref "L27") (pin "2") (pinfunction "2_2") (pintype "passive"))
      (node (ref "R211") (pin "1") (pinfunction "1_1") (pintype "passive"))
    )
    (net (code "38") (name "Net-(C301-Pad1)") (class "Default")
      (node (ref "C301") (pin "1") (pinfunction "1_1") (pintype "passive"))
      (node (ref "J42") (pin "1") (pinfunction "1_1") (pintype "passive"))
      (node (ref "L19") (pin "2") (pinfunction "2_2") (pintype "passive"))
      (node (ref "R210") (pin "1") (pinfunction "1_1") (pintype "passive"))
    )
    (net (code "39") (name "Net-(C308-Pad2)") (class "Default")
      (node (ref "C308") (pin "2") (pinfunction "2_2") (pintype "passive"))
      (node (ref "R349") (pin "1") (pinfunction "1_1") (pintype "passive"))
    )
    (net (code "40") (name "Net-(C309-Pad2)") (class "Default")
      (node (ref "C309") (pin "2") (pinfunction "2_2") (pintype "passive"))
      (node (ref "R350") (pin "1") (pinfunction "1_1") (pintype "passive"))
    )
    (net (code "41") (name "Net-(C310-Pad1)") (class "Default")
      (node (ref "C310") (pin "1") (pinfunction "1_1") (pintype "passive"))
      (node (ref "J43") (pin "2") (pinfunction "2_2") (pintype "passive"))
      (node (ref "L29") (pin "2") (pinfunction "2_2") (pintype "passive"))
      (node (ref "R213") (pin "1") (pinfunction "1_1") (pintype "passive"))
    )
    (net (code "42") (name "Net-(C311-Pad1)") (class "Default")
      (node (ref "C311") (pin "1") (pinfunction "1_1") (pintype "passive"))
      (node (ref "J43") (pin "1") (pinfunction "1_1") (pintype "passive"))
      (node (ref "L28") (pin "2") (pinfunction "2_2") (pintype "passive"))
      (node (ref "R212") (pin "1") (pinfunction "1_1") (pintype "passive"))
    )
    (net (code "43") (name "Net-(D15-K)") (class "Default")
      (node (ref "D15") (pin "1") (pinfunction "K_1") (pintype "passive"))
      (node (ref "J12") (pin "1") (pinfunction "1_1") (pintype "passive"))
      (node (ref "R129") (pin "2") (pinfunction "2_2") (pintype "passive"))
    )
    (net (code "44") (name "Net-(J11-Pad2)") (class "Default")
      (node (ref "J11") (pin "2") (pinfunction "2_2") (pintype "passive"))
      (node (ref "R327") (pin "1") (pinfunction "1_1") (pintype "passive"))
    )
    (net (code "45") (name "Net-(LED2-A)") (class "Default")
      (node (ref "LED2") (pin "1") (pinfunction "A_1") (pintype "passive"))
      (node (ref "R128") (pin "2") (pinfunction "2_2") (pintype "passive"))
    )
    (net (code "46") (name "Net-(LED2-K)") (class "Default")
      (node (ref "LED2") (pin "2") (pinfunction "K_2") (pintype "passive"))
      (node (ref "Q35") (pin "3") (pinfunction "COLLECTOR_3") (pintype "passive"))
    )
    (net (code "47") (name "Net-(P1-GND)") (class "Default")
      (node (ref "C126") (pin "2") (pinfunction "2_2") (pintype "passive"))
      (node (ref "D78") (pin "2") (pinfunction "2_2") (pintype "passive"))
      (node (ref "P1") (pin "2") (pinfunction "GND_2") (pintype "passive"))
      (node (ref "R134") (pin "1") (pinfunction "1_1") (pintype "passive"))
      (node (ref "R136") (pin "1") (pinfunction "1_1") (pintype "passive"))
    )
    (net (code "48") (name "Net-(P1-Out)") (class "Default")
      (node (ref "C126") (pin "1") (pinfunction "1_1") (pintype "passive"))
      (node (ref "D83") (pin "2") (pinfunction "2_2") (pintype "passive"))
      (node (ref "P1") (pin "1") (pinfunction "Out_1") (pintype "passive"))
      (node (ref "R126") (pin "2") (pinfunction "2_2") (pintype "passive"))
      (node (ref "R130") (pin "1") (pinfunction "1_1") (pintype "passive"))
    )
    (net (code "49") (name "Net-(Q1-DRAIN)") (class "Default")
      (node (ref "Q1") (pin "3") (pinfunction "DRAIN_3") (pintype "passive"))
      (node (ref "R129") (pin "1") (pinfunction "1_1") (pintype "passive"))
    )
    (net (code "50") (name "Net-(Q1-GATE)") (class "Default")
      (node (ref "Q1") (pin "1") (pinfunction "GATE_1") (pintype "passive"))
      (node (ref "Q2") (pin "3") (pinfunction "COLLECTOR_3") (pintype "passive"))
      (node (ref "R132") (pin "2") (pinfunction "2_2") (pintype "passive"))
    )
    (net (code "51") (name "Net-(Q1-SOURCE)") (class "Default")
      (node (ref "Q1") (pin "2") (pinfunction "SOURCE_2") (pintype "passive"))
      (node (ref "R127") (pin "2") (pinfunction "2_2") (pintype "passive"))
      (node (ref "R131") (pin "2") (pinfunction "2_2") (pintype "passive"))
      (node (ref "R132") (pin "1") (pinfunction "1_1") (pintype "passive"))
    )
    (net (code "52") (name "Net-(Q2-BASE)") (class "Default")
      (node (ref "Q2") (pin "1") (pinfunction "BASE_1") (pintype "input"))
      (node (ref "R133") (pin "2") (pinfunction "2_2") (pintype "passive"))
      (node (ref "R135") (pin "1") (pinfunction "1_1") (pintype "passive"))
    )
    (net (code "53") (name "Net-(Q3-DRAIN)") (class "Default")
      (node (ref "Q3") (pin "3") (pinfunction "DRAIN_3") (pintype "passive"))
      (node (ref "R122") (pin "1") (pinfunction "1_1") (pintype "passive"))
      (node (ref "R123") (pin "1") (pinfunction "1_1") (pintype "passive"))
    )
    (net (code "54") (name "Net-(Q3-GATE)") (class "Default")
      (node (ref "C289") (pin "1") (pinfunction "1_1") (pintype "passive"))
      (node (ref "Q3") (pin "1") (pinfunction "GATE_1") (pintype "passive"))
      (node (ref "Q4") (pin "1") (pinfunction "GATE_1") (pintype "passive"))
      (node (ref "R326") (pin "1") (pinfunction "1_1") (pintype "passive"))
    )
    (net (code "55") (name "Net-(Q3-SOURCE)") (class "Default")
      (node (ref "D79") (pin "2") (pinfunction "2_2") (pintype "passive"))
      (node (ref "J11") (pin "4") (pinfunction "4_4") (pintype "passive"))
      (node (ref "Q3") (pin "2") (pinfunction "SOURCE_2") (pintype "passive"))
    )
    (net (code "56") (name "Net-(Q4-DRAIN)") (class "Default")
      (node (ref "Q4") (pin "3") (pinfunction "DRAIN_3") (pintype "passive"))
      (node (ref "R124") (pin "1") (pinfunction "1_1") (pintype "passive"))
      (node (ref "R325") (pin "1") (pinfunction "1_1") (pintype "passive"))
    )
    (net (code "57") (name "Net-(Q4-SOURCE)") (class "Default")
      (node (ref "D80") (pin "2") (pinfunction "2_2") (pintype "passive"))
      (node (ref "J11") (pin "3") (pinfunction "3_3") (pintype "passive"))
      (node (ref "Q4") (pin "2") (pinfunction "SOURCE_2") (pintype "passive"))
    )
    (net (code "58") (name "Net-(Q35-BASE)") (class "Default")
      (node (ref "Q35") (pin "1") (pinfunction "BASE_1") (pintype "input"))
      (node (ref "R334") (pin "2") (pinfunction "2_2") (pintype "passive"))
      (node (ref "R335") (pin "1") (pinfunction "1_1") (pintype "passive"))
    )
    (net (code "59") (name "Net-(SPK1-Pad1)") (class "Default")
      (node (ref "SPK1") (pin "1") (pinfunction "1_1") (pintype "passive"))
      (node (ref "SW5") (pin "2") (pinfunction "2_2") (pintype "passive"))
    )
    (net (code "60") (name "Net-(SPK1-Pad2)") (class "Default")
      (node (ref "SPK1") (pin "2") (pinfunction "2_2") (pintype "passive"))
      (node (ref "SW5") (pin "5") (pinfunction "5_5") (pintype "passive"))
    )
    (net (code "61") (name "Net-(U16-ADCVREF)") (class "Default")
      (node (ref "C119") (pin "1") (pinfunction "1_1") (pintype "passive"))
      (node (ref "U16") (pin "19") (pinfunction "ADCVREF_19") (pintype "passive"))
    )
    (net (code "62") (name "Net-(U16-AVDD)") (class "Default")
      (node (ref "C106") (pin "1") (pinfunction "1_1") (pintype "passive"))
      (node (ref "C107") (pin "1") (pinfunction "1_1") (pintype "passive"))
      (node (ref "R112") (pin "1") (pinfunction "1_1") (pintype "passive"))
      (node (ref "U16") (pin "17") (pinfunction "AVDD_17") (pintype "passive"))
    )
    (net (code "63") (name "Net-(U16-CE)") (class "Default")
      (node (ref "R121") (pin "2") (pinfunction "2_2") (pintype "passive"))
      (node (ref "U16") (pin "26") (pinfunction "CE_26") (pintype "passive"))
    )
    (net (code "64") (name "Net-(U16-LIN1)") (class "Default")
      (node (ref "C112") (pin "1") (pinfunction "1_1") (pintype "passive"))
      (node (ref "U16") (pin "24") (pinfunction "LIN1_24") (pintype "passive"))
    )
    (net (code "65") (name "Net-(U16-LIN2)") (class "Default")
      (node (ref "C115") (pin "1") (pinfunction "1_1") (pintype "passive"))
      (node (ref "U16") (pin "22") (pinfunction "LIN2_22") (pintype "passive"))
    )
    (net (code "66") (name "Net-(U16-RIN1)") (class "Default")
      (node (ref "C113") (pin "1") (pinfunction "1_1") (pintype "passive"))
      (node (ref "U16") (pin "23") (pinfunction "RIN1_23") (pintype "passive"))
    )
    (net (code "67") (name "Net-(U16-RIN2)") (class "Default")
      (node (ref "C117") (pin "1") (pinfunction "1_1") (pintype "passive"))
      (node (ref "U16") (pin "21") (pinfunction "RIN2_21") (pintype "passive"))
    )
    (net (code "68") (name "Net-(U16-VMID)") (class "Default")
      (node (ref "C118") (pin "1") (pinfunction "1_1") (pintype "passive"))
      (node (ref "U16") (pin "20") (pinfunction "VMID_20") (pintype "passive"))
    )
    (net (code "69") (name "Net-(U16-VREF)") (class "Default")
      (node (ref "C120") (pin "1") (pinfunction "1_1") (pintype "passive"))
      (node (ref "U16") (pin "10") (pinfunction "VREF_10") (pintype "passive"))
    )
    (net (code "70") (name "Net-(U42-BYPASS)") (class "Default")
      (node (ref "C302") (pin "1") (pinfunction "1_1") (pintype "passive"))
      (node (ref "U42") (pin "2") (pinfunction "BYPASS_2") (pintype "passive"))
    )
    (net (code "71") (name "Net-(U42-CTRL)") (class "Default")
      (node (ref "R345") (pin "2") (pinfunction "2_2") (pintype "passive"))
      (node (ref "R346") (pin "1") (pinfunction "1_1") (pintype "passive"))
      (node (ref "U42") (pin "1") (pinfunction "CTRL_1") (pintype "passive"))
    )
    (net (code "72") (name "Net-(U42-INN)") (class "Default")
      (node (ref "R343") (pin "2") (pinfunction "2_2") (pintype "passive"))
      (node (ref "U42") (pin "4") (pinfunction "INN_4") (pintype "passive"))
    )
    (net (code "73") (name "Net-(U42-INP)") (class "Default")
      (node (ref "R344") (pin "2") (pinfunction "2_2") (pintype "passive"))
      (node (ref "U42") (pin "3") (pinfunction "INP_3") (pintype "passive"))
    )
    (net (code "74") (name "Net-(U42-VDD)") (class "Default")
      (node (ref "C210") (pin "1") (pinfunction "1_1") (pintype "passive"))
      (node (ref "C211") (pin "1") (pinfunction "1_1") (pintype "passive"))
      (node (ref "C218") (pin "1") (pinfunction "1_1") (pintype "passive"))
      (node (ref "C219") (pin "1") (pinfunction "1_1") (pintype "passive"))
      (node (ref "C278") (pin "1") (pinfunction "1_1") (pintype "passive"))
      (node (ref "R341") (pin "2") (pinfunction "2_2") (pintype "passive"))
      (node (ref "R342") (pin "2") (pinfunction "2_2") (pintype "passive"))
      (node (ref "U42") (pin "6") (pinfunction "VDD_6") (pintype "passive"))
    )
    (net (code "75") (name "Net-(U42-VON)") (class "Default")
      (node (ref "L19") (pin "1") (pinfunction "1_1") (pintype "passive"))
      (node (ref "U42") (pin "5") (pinfunction "VON_5") (pintype "passive"))
    )
    (net (code "76") (name "Net-(U42-VOP)") (class "Default")
      (node (ref "L27") (pin "1") (pinfunction "1_1") (pintype "passive"))
      (node (ref "U42") (pin "8") (pinfunction "VOP_8") (pintype "passive"))
    )
    (net (code "77") (name "Net-(U46-BYPASS)") (class "Default")
      (node (ref "C312") (pin "1") (pinfunction "1_1") (pintype "passive"))
      (node (ref "U46") (pin "2") (pinfunction "BYPASS_2") (pintype "passive"))
    )
    (net (code "78") (name "Net-(U46-CTRL)") (class "Default")
      (node (ref "R351") (pin "2") (pinfunction "2_2") (pintype "passive"))
      (node (ref "R352") (pin "1") (pinfunction "1_1") (pintype "passive"))
      (node (ref "U46") (pin "1") (pinfunction "CTRL_1") (pintype "passive"))
    )
    (net (code "79") (name "Net-(U46-INN)") (class "Default")
      (node (ref "R349") (pin "2") (pinfunction "2_2") (pintype "passive"))
      (node (ref "U46") (pin "4") (pinfunction "INN_4") (pintype "passive"))
    )
    (net (code "80") (name "Net-(U46-INP)") (class "Default")
      (node (ref "R350") (pin "2") (pinfunction "2_2") (pintype "passive"))
      (node (ref "U46") (pin "3") (pinfunction "INP_3") (pintype "passive"))
    )
    (net (code "81") (name "Net-(U46-VDD)") (class "Default")
      (node (ref "C303") (pin "1") (pinfunction "1_1") (pintype "passive"))
      (node (ref "C304") (pin "1") (pinfunction "1_1") (pintype "passive"))
      (node (ref "C305") (pin "1") (pinfunction "1_1") (pintype "passive"))
      (node (ref "C306") (pin "1") (pinfunction "1_1") (pintype "passive"))
      (node (ref "C307") (pin "1") (pinfunction "1_1") (pintype "passive"))
      (node (ref "R347") (pin "2") (pinfunction "2_2") (pintype "passive"))
      (node (ref "R348") (pin "2") (pinfunction "2_2") (pintype "passive"))
      (node (ref "U46") (pin "6") (pinfunction "VDD_6") (pintype "passive"))
    )
    (net (code "82") (name "Net-(U46-VON)") (class "Default")
      (node (ref "L28") (pin "1") (pinfunction "1_1") (pintype "passive"))
      (node (ref "U46") (pin "5") (pinfunction "VON_5") (pintype "passive"))
    )
    (net (code "83") (name "Net-(U46-VOP)") (class "Default")
      (node (ref "L29") (pin "1") (pinfunction "1_1") (pintype "passive"))
      (node (ref "U46") (pin "8") (pinfunction "VOP_8") (pintype "passive"))
    )
    (net (code "84") (name "SPK_CTRL") (class "Default")
      (node (ref "R345") (pin "1") (pinfunction "1_1") (pintype "passive"))
      (node (ref "R351") (pin "1") (pinfunction "1_1") (pintype "passive"))
    )
    (net (code "85") (name "SYS_LED") (class "Default")
      (node (ref "R334") (pin "1") (pinfunction "1_1") (pintype "passive"))
    )
    (net (code "86") (name "VCCA1V8_CODEC") (class "Default")
      (node (ref "C108") (pin "1") (pinfunction "1_1") (pintype "passive"))
      (node (ref "C114") (pin "1") (pinfunction "1_1") (pintype "passive"))
      (node (ref "C123") (pin "1") (pinfunction "1_1") (pintype "passive"))
      (node (ref "L14") (pin "2") (pinfunction "2_2") (pintype "passive"))
      (node (ref "L4") (pin "2") (pinfunction "2_2") (pintype "passive"))
      (node (ref "R121") (pin "1") (pinfunction "1_1") (pintype "passive"))
      (node (ref "U16") (pin "2") (pinfunction "DVDD_2") (pintype "passive"))
      (node (ref "U16") (pin "3") (pinfunction "PVDD_3") (pintype "passive"))
    )
    (net (code "87") (name "VCCA3V3_CODEC") (class "Default")
      (node (ref "C109") (pin "1") (pinfunction "1_1") (pintype "passive"))
      (node (ref "C110") (pin "1") (pinfunction "1_1") (pintype "passive"))
      (node (ref "C124") (pin "1") (pinfunction "1_1") (pintype "passive"))
      (node (ref "L15") (pin "2") (pinfunction "2_2") (pintype "passive"))
      (node (ref "L5") (pin "2") (pinfunction "2_2") (pintype "passive"))
      (node (ref "R112") (pin "2") (pinfunction "2_2") (pintype "passive"))
      (node (ref "R113") (pin "2") (pinfunction "2_2") (pintype "passive"))
      (node (ref "R125") (pin "1") (pinfunction "1_1") (pintype "passive"))
      (node (ref "U16") (pin "16") (pinfunction "HPVDD_16") (pintype "passive"))
    )
    (net (code "88") (name "VCC_3V3_S0") (class "Default")
      (node (ref "L15") (pin "1") (pinfunction "1_1") (pintype "passive"))
      (node (ref "R128") (pin "1") (pinfunction "1_1") (pintype "passive"))
    )
    (net (code "89") (name "VCC_5V0_S0") (class "Default")
      (node (ref "R127") (pin "1") (pinfunction "1_1") (pintype "passive"))
      (node (ref "R342") (pin "1") (pinfunction "1_1") (pintype "passive"))
      (node (ref "R348") (pin "1") (pinfunction "1_1") (pintype "passive"))
    )
    (net (code "90") (name "VCC_12V") (class "Default")
      (node (ref "R131") (pin "1") (pinfunction "1_1") (pintype "passive"))
      (node (ref "R341") (pin "1") (pinfunction "1_1") (pintype "passive"))
      (node (ref "R347") (pin "1") (pinfunction "1_1") (pintype "passive"))
    )
    (net (code "91") (name "unconnected-(J11-Pad7)") (class "Default")
      (node (ref "J11") (pin "7") (pinfunction "7_7") (pintype "passive+no_connect"))
    )
    (net (code "92") (name "unconnected-(J11-Pad8)") (class "Default")
      (node (ref "J11") (pin "8") (pinfunction "8_8") (pintype "passive+no_connect"))
    )
    (net (code "93") (name "unconnected-(U16-NC1-Pad9)") (class "Default")
      (node (ref "U16") (pin "9") (pinfunction "NC1_9") (pintype "passive+no_connect"))
    )
    (net (code "94") (name "unconnected-(U16-NC2-Pad25)") (class "Default")
      (node (ref "U16") (pin "25") (pinfunction "NC2_25") (pintype "passive+no_connect"))
    )
  )
)
